# rat.net
KiCad netlist of a schematic drawn in EAGLE
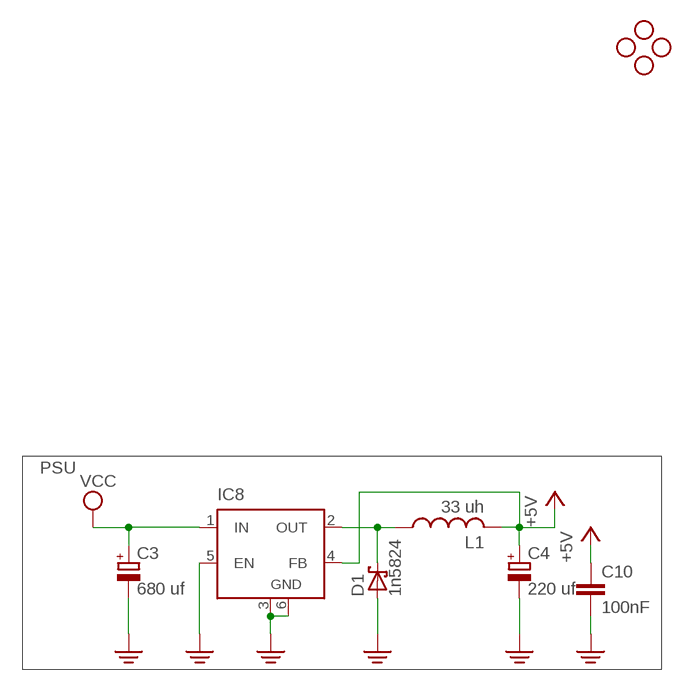
[diagram p0: schematic, sheet 1, part 1 of 2]
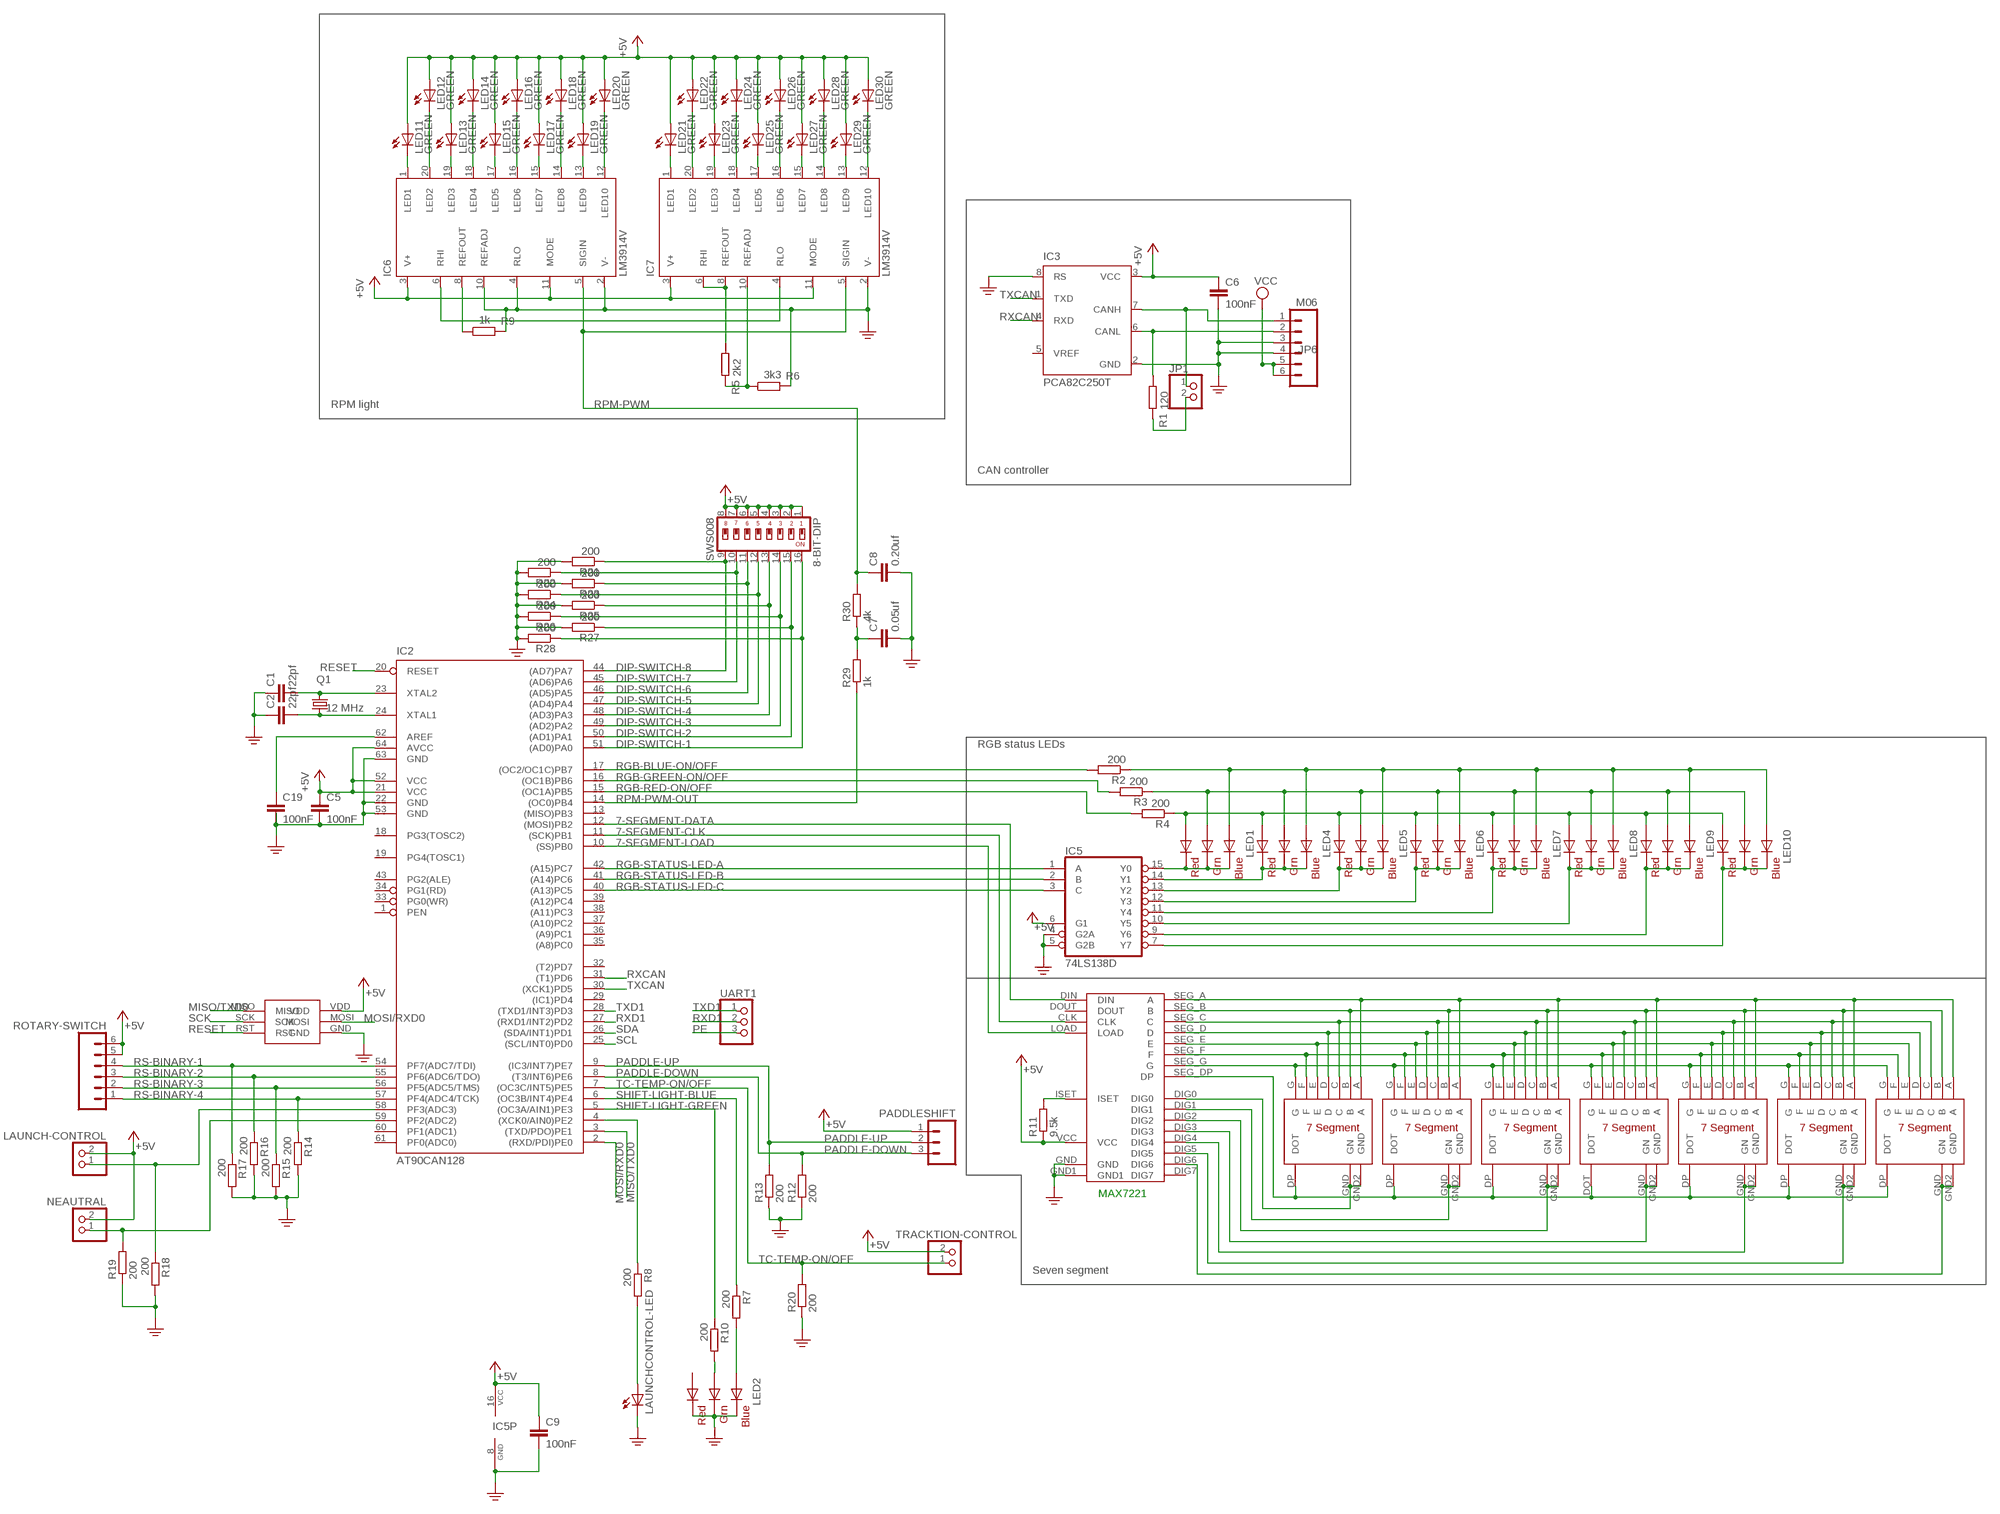
[diagram p1: schematic, sheet 1, part 2 of 2]

(export (version "E")
  (design (tool "Eeschema 10.0.6"))
  (components
    (comp (ref "8-BIT-DIP")
      (value "SWS008")
      (footprint "eagle-import:SMS-008")
      (libsource (lib "eagle-import") (part "SWS008"))
    )
    (comp (ref "C1")
      (value "22pf")
      (footprint "eagle-import:C0603K")
      (libsource (lib "eagle-import") (part "C-EUC0603K"))
    )
    (comp (ref "C2")
      (value "22pf")
      (footprint "eagle-import:C0603K")
      (libsource (lib "eagle-import") (part "C-EUC0603K"))
    )
    (comp (ref "C3")
      (value "680 uf")
      (footprint "eagle-import:E5-10,5")
      (libsource (lib "eagle-import") (part "CPOL-EUE5-10.5"))
    )
    (comp (ref "C4")
      (value "220 uf")
      (footprint "eagle-import:E2,5-7")
      (libsource (lib "eagle-import") (part "CPOL-EUE2.5-7"))
    )
    (comp (ref "C5")
      (value "100nF")
      (footprint "eagle-import:C0603K")
      (libsource (lib "eagle-import") (part "C-EUC0603K"))
    )
    (comp (ref "C6")
      (value "100nF")
      (footprint "eagle-import:C0603K")
      (libsource (lib "eagle-import") (part "C-EUC0603K"))
    )
    (comp (ref "C7")
      (value "0.05uf")
      (footprint "eagle-import:C0603K")
      (libsource (lib "eagle-import") (part "C-EUC0603K"))
    )
    (comp (ref "C8")
      (value "0.20uf")
      (footprint "eagle-import:C0603K")
      (libsource (lib "eagle-import") (part "C-EUC0603K"))
    )
    (comp (ref "C9")
      (value "100nF")
      (footprint "eagle-import:C0603K")
      (libsource (lib "eagle-import") (part "C-EUC0603K"))
    )
    (comp (ref "C10")
      (value "100nF")
      (footprint "eagle-import:C0603K")
      (libsource (lib "eagle-import") (part "C-EUC0603K"))
    )
    (comp (ref "C19")
      (value "100nF")
      (footprint "eagle-import:C0603K")
      (libsource (lib "eagle-import") (part "C-EUC0603K"))
    )
    (comp (ref "D1")
      (value "1n5824")
      (footprint "eagle-import:P6T15")
      (libsource (lib "eagle-import") (part "SCHOTTKY-DIODEP6T15"))
    )
    (comp (ref "IC2")
      (value "AT90CAN128")
      (footprint "eagle-import:TQFP64")
      (fields (field (name "MPN") "ATMEGA128-16AU"))
      (libsource (lib "eagle-import") (part "MEGA128-A"))
    )
    (comp (ref "IC3")
      (value "PCA82C250T")
      (footprint "eagle-import:SO8")
      (libsource (lib "eagle-import") (part "PCA82C250T"))
    )
    (comp (ref "IC5")
      (value "74LS138D")
      (footprint "eagle-import:SO16")
      (libsource (lib "eagle-import") (part "74138DLS"))
    )
    (comp (ref "IC6")
      (value "LM3914V")
      (footprint "eagle-import:PLCC20S")
      (libsource (lib "eagle-import") (part "LM391V4"))
    )
    (comp (ref "IC7")
      (value "LM3914V")
      (footprint "eagle-import:PLCC20S")
      (libsource (lib "eagle-import") (part "LM391V4"))
    )
    (comp (ref "IC8")
      (value "LM2596S")
      (footprint "eagle-import:TO263-5")
      (libsource (lib "eagle-import") (part "LM2596S"))
    )
    (comp (ref "JP1")
      (value "PINHD-1X2")
      (footprint "eagle-import:1X02")
      (libsource (lib "eagle-import") (part "PINHD-1X2"))
    )
    (comp (ref "JP2")
      (value "STAND-OFF")
      (footprint "eagle-import:STAND-OFF")
      (libsource (lib "eagle-import") (part "STAND-OFF"))
    )
    (comp (ref "JP3")
      (value "STAND-OFF")
      (footprint "eagle-import:STAND-OFF")
      (libsource (lib "eagle-import") (part "STAND-OFF"))
    )
    (comp (ref "JP4")
      (value "STAND-OFF")
      (footprint "eagle-import:STAND-OFF")
      (libsource (lib "eagle-import") (part "STAND-OFF"))
    )
    (comp (ref "JP5")
      (value "STAND-OFF")
      (footprint "eagle-import:STAND-OFF")
      (libsource (lib "eagle-import") (part "STAND-OFF"))
    )
    (comp (ref "JP6")
      (value "M06")
      (footprint "eagle-import:S6B_PH")
      (libsource (lib "eagle-import") (part "M06"))
    )
    (comp (ref "L1")
      (value "33 uh")
      (footprint "eagle-import:TFI0410")
      (libsource (lib "eagle-import") (part "L-USTFI0410"))
    )
    (comp (ref "LAUNCH-CONTROL")
      (value "JST_2PIN-SMT-RA")
      (footprint "eagle-import:JST-PH-2-SMT-RA")
      (libsource (lib "eagle-import") (part "JST_2PIN-SMT-RA"))
    )
    (comp (ref "LAUNCHCONTROL-LED")
      (value "LEDSMT1206")
      (footprint "eagle-import:1206")
      (libsource (lib "eagle-import") (part "LEDSMT1206"))
    )
    (comp (ref "LED1")
      (value "RGBLED5050")
      (footprint "eagle-import:RGBLED5050")
      (libsource (lib "eagle-import") (part "RGBLED5050"))
    )
    (comp (ref "LED2")
      (value "RGBLED5050")
      (footprint "eagle-import:RGBLED5050")
      (libsource (lib "eagle-import") (part "RGBLED5050"))
    )
    (comp (ref "LED4")
      (value "RGBLED5050")
      (footprint "eagle-import:RGBLED5050")
      (libsource (lib "eagle-import") (part "RGBLED5050"))
    )
    (comp (ref "LED5")
      (value "RGBLED5050")
      (footprint "eagle-import:RGBLED5050")
      (libsource (lib "eagle-import") (part "RGBLED5050"))
    )
    (comp (ref "LED6")
      (value "RGBLED5050")
      (footprint "eagle-import:RGBLED5050")
      (libsource (lib "eagle-import") (part "RGBLED5050"))
    )
    (comp (ref "LED7")
      (value "RGBLED5050")
      (footprint "eagle-import:RGBLED5050")
      (libsource (lib "eagle-import") (part "RGBLED5050"))
    )
    (comp (ref "LED8")
      (value "RGBLED5050")
      (footprint "eagle-import:RGBLED5050")
      (libsource (lib "eagle-import") (part "RGBLED5050"))
    )
    (comp (ref "LED9")
      (value "RGBLED5050")
      (footprint "eagle-import:RGBLED5050")
      (libsource (lib "eagle-import") (part "RGBLED5050"))
    )
    (comp (ref "LED10")
      (value "RGBLED5050")
      (footprint "eagle-import:RGBLED5050")
      (libsource (lib "eagle-import") (part "RGBLED5050"))
    )
    (comp (ref "LED11")
      (value "GREEN")
      (footprint "eagle-import:1206")
      (libsource (lib "eagle-import") (part "LEDSMT1206"))
    )
    (comp (ref "LED12")
      (value "GREEN")
      (footprint "eagle-import:1206")
      (libsource (lib "eagle-import") (part "LEDSMT1206"))
    )
    (comp (ref "LED13")
      (value "GREEN")
      (footprint "eagle-import:1206")
      (libsource (lib "eagle-import") (part "LEDSMT1206"))
    )
    (comp (ref "LED14")
      (value "GREEN")
      (footprint "eagle-import:1206")
      (libsource (lib "eagle-import") (part "LEDSMT1206"))
    )
    (comp (ref "LED15")
      (value "GREEN")
      (footprint "eagle-import:1206")
      (libsource (lib "eagle-import") (part "LEDSMT1206"))
    )
    (comp (ref "LED16")
      (value "GREEN")
      (footprint "eagle-import:1206")
      (libsource (lib "eagle-import") (part "LEDSMT1206"))
    )
    (comp (ref "LED17")
      (value "GREEN")
      (footprint "eagle-import:1206")
      (libsource (lib "eagle-import") (part "LEDSMT1206"))
    )
    (comp (ref "LED18")
      (value "GREEN")
      (footprint "eagle-import:1206")
      (libsource (lib "eagle-import") (part "LEDSMT1206"))
    )
    (comp (ref "LED19")
      (value "GREEN")
      (footprint "eagle-import:1206")
      (libsource (lib "eagle-import") (part "LEDSMT1206"))
    )
    (comp (ref "LED20")
      (value "GREEN")
      (footprint "eagle-import:1206")
      (libsource (lib "eagle-import") (part "LEDSMT1206"))
    )
    (comp (ref "LED21")
      (value "GREEN")
      (footprint "eagle-import:1206")
      (libsource (lib "eagle-import") (part "LEDSMT1206"))
    )
    (comp (ref "LED22")
      (value "GREEN")
      (footprint "eagle-import:1206")
      (libsource (lib "eagle-import") (part "LEDSMT1206"))
    )
    (comp (ref "LED23")
      (value "GREEN")
      (footprint "eagle-import:1206")
      (libsource (lib "eagle-import") (part "LEDSMT1206"))
    )
    (comp (ref "LED24")
      (value "GREEN")
      (footprint "eagle-import:1206")
      (libsource (lib "eagle-import") (part "LEDSMT1206"))
    )
    (comp (ref "LED25")
      (value "GREEN")
      (footprint "eagle-import:1206")
      (libsource (lib "eagle-import") (part "LEDSMT1206"))
    )
    (comp (ref "LED26")
      (value "GREEN")
      (footprint "eagle-import:1206")
      (libsource (lib "eagle-import") (part "LEDSMT1206"))
    )
    (comp (ref "LED27")
      (value "GREEN")
      (footprint "eagle-import:1206")
      (libsource (lib "eagle-import") (part "LEDSMT1206"))
    )
    (comp (ref "LED28")
      (value "GREEN")
      (footprint "eagle-import:1206")
      (libsource (lib "eagle-import") (part "LEDSMT1206"))
    )
    (comp (ref "LED29")
      (value "GREEN")
      (footprint "eagle-import:1206")
      (libsource (lib "eagle-import") (part "LEDSMT1206"))
    )
    (comp (ref "LED30")
      (value "GREEN")
      (footprint "eagle-import:1206")
      (libsource (lib "eagle-import") (part "LEDSMT1206"))
    )
    (comp (ref "MAX7221")
      (value "MAX7221-SMD")
      (footprint "eagle-import:MAX7221")
      (libsource (lib "eagle-import") (part "MAX7221-SMD"))
    )
    (comp (ref "NEAUTRAL")
      (value "JST_2PIN-SMT-RA")
      (footprint "eagle-import:JST-PH-2-SMT-RA")
      (libsource (lib "eagle-import") (part "JST_2PIN-SMT-RA"))
    )
    (comp (ref "PADDLESHIFT")
      (value "M03")
      (footprint "eagle-import:S3B-PH")
      (libsource (lib "eagle-import") (part "M03"))
    )
    (comp (ref "Q1")
      (value "12 MHz")
      (footprint "eagle-import:HC49U70")
      (libsource (lib "eagle-import") (part "CRYSTALHC49U70"))
    )
    (comp (ref "R1")
      (value "120")
      (footprint "eagle-import:R0603")
      (libsource (lib "eagle-import") (part "resistor_R-EU_R0603"))
    )
    (comp (ref "R2")
      (value "200")
      (footprint "eagle-import:R0603")
      (libsource (lib "eagle-import") (part "R-EU_R0603"))
    )
    (comp (ref "R3")
      (value "200")
      (footprint "eagle-import:R0603")
      (libsource (lib "eagle-import") (part "R-EU_R0603"))
    )
    (comp (ref "R4")
      (value "200")
      (footprint "eagle-import:R0603")
      (libsource (lib "eagle-import") (part "R-EU_R0603"))
    )
    (comp (ref "R5")
      (value "2k2")
      (footprint "eagle-import:R0603")
      (libsource (lib "eagle-import") (part "resistor_R-EU_R0603"))
    )
    (comp (ref "R6")
      (value "3k3")
      (footprint "eagle-import:R0603")
      (libsource (lib "eagle-import") (part "resistor_R-EU_R0603"))
    )
    (comp (ref "R7")
      (value "200")
      (footprint "eagle-import:R0603")
      (libsource (lib "eagle-import") (part "R-EU_R0603"))
    )
    (comp (ref "R8")
      (value "200")
      (footprint "eagle-import:R0603")
      (libsource (lib "eagle-import") (part "R-EU_R0603"))
    )
    (comp (ref "R9")
      (value "1k")
      (footprint "eagle-import:R0603")
      (libsource (lib "eagle-import") (part "resistor_R-EU_R0603"))
    )
    (comp (ref "R10")
      (value "200")
      (footprint "eagle-import:R0603")
      (libsource (lib "eagle-import") (part "R-EU_R0603"))
    )
    (comp (ref "R11")
      (value "9.5k")
      (footprint "eagle-import:R0603")
      (libsource (lib "eagle-import") (part "R-EU_R0603"))
    )
    (comp (ref "R12")
      (value "200")
      (footprint "eagle-import:R0603")
      (libsource (lib "eagle-import") (part "R-EU_R0603"))
    )
    (comp (ref "R13")
      (value "200")
      (footprint "eagle-import:R0603")
      (libsource (lib "eagle-import") (part "R-EU_R0603"))
    )
    (comp (ref "R14")
      (value "200")
      (footprint "eagle-import:R0603")
      (libsource (lib "eagle-import") (part "R-EU_R0603"))
    )
    (comp (ref "R15")
      (value "200")
      (footprint "eagle-import:R0603")
      (libsource (lib "eagle-import") (part "R-EU_R0603"))
    )
    (comp (ref "R16")
      (value "200")
      (footprint "eagle-import:R0603")
      (libsource (lib "eagle-import") (part "R-EU_R0603"))
    )
    (comp (ref "R17")
      (value "200")
      (footprint "eagle-import:R0603")
      (libsource (lib "eagle-import") (part "R-EU_R0603"))
    )
    (comp (ref "R18")
      (value "200")
      (footprint "eagle-import:R0603")
      (libsource (lib "eagle-import") (part "R-EU_R0603"))
    )
    (comp (ref "R19")
      (value "200")
      (footprint "eagle-import:R0603")
      (libsource (lib "eagle-import") (part "R-EU_R0603"))
    )
    (comp (ref "R20")
      (value "200")
      (footprint "eagle-import:R0603")
      (libsource (lib "eagle-import") (part "R-EU_R0603"))
    )
    (comp (ref "R21")
      (value "200")
      (footprint "eagle-import:R0603")
      (libsource (lib "eagle-import") (part "R-EU_R0603"))
    )
    (comp (ref "R22")
      (value "200")
      (footprint "eagle-import:R0603")
      (libsource (lib "eagle-import") (part "R-EU_R0603"))
    )
    (comp (ref "R23")
      (value "200")
      (footprint "eagle-import:R0603")
      (libsource (lib "eagle-import") (part "R-EU_R0603"))
    )
    (comp (ref "R24")
      (value "200")
      (footprint "eagle-import:R0603")
      (libsource (lib "eagle-import") (part "R-EU_R0603"))
    )
    (comp (ref "R25")
      (value "200")
      (footprint "eagle-import:R0603")
      (libsource (lib "eagle-import") (part "R-EU_R0603"))
    )
    (comp (ref "R26")
      (value "200")
      (footprint "eagle-import:R0603")
      (libsource (lib "eagle-import") (part "R-EU_R0603"))
    )
    (comp (ref "R27")
      (value "200")
      (footprint "eagle-import:R0603")
      (libsource (lib "eagle-import") (part "R-EU_R0603"))
    )
    (comp (ref "R28")
      (value "200")
      (footprint "eagle-import:R0603")
      (libsource (lib "eagle-import") (part "R-EU_R0603"))
    )
    (comp (ref "R29")
      (value "1k")
      (footprint "eagle-import:R0603")
      (libsource (lib "eagle-import") (part "R-EU_R0603"))
    )
    (comp (ref "R30")
      (value "4k")
      (footprint "eagle-import:R0603")
      (libsource (lib "eagle-import") (part "R-EU_R0603"))
    )
    (comp (ref "ROTARY-SWITCH")
      (value "M06")
      (footprint "eagle-import:S6B_PH")
      (libsource (lib "eagle-import") (part "M06"))
    )
    (comp (ref "TRACKTION-CONTROL")
      (value "JST_2PIN-SMT-RA")
      (footprint "eagle-import:JST-PH-2-SMT-RA")
      (libsource (lib "eagle-import") (part "JST_2PIN-SMT-RA"))
    )
    (comp (ref "U$2")
      (value "REDSEVENSEGMENT")
      (footprint "eagle-import:REDSEGMENT")
      (libsource (lib "eagle-import") (part "REDSEVENSEGMENT"))
    )
    (comp (ref "U$3")
      (value "REDSEVENSEGMENT")
      (footprint "eagle-import:REDSEGMENT")
      (libsource (lib "eagle-import") (part "REDSEVENSEGMENT"))
    )
    (comp (ref "U$4")
      (value "REDSEVENSEGMENT")
      (footprint "eagle-import:REDSEGMENT")
      (libsource (lib "eagle-import") (part "REDSEVENSEGMENT"))
    )
    (comp (ref "U$5")
      (value "BIGSEVENSEGMENT")
      (footprint "eagle-import:BIGSEVENSEGMENT")
      (libsource (lib "eagle-import") (part "BIGSEVENSEGMENT"))
    )
    (comp (ref "U$6")
      (value "REDSEVENSEGMENT")
      (footprint "eagle-import:REDSEGMENT")
      (libsource (lib "eagle-import") (part "REDSEVENSEGMENT"))
    )
    (comp (ref "U$7")
      (value "REDSEVENSEGMENT")
      (footprint "eagle-import:REDSEGMENT")
      (libsource (lib "eagle-import") (part "REDSEVENSEGMENT"))
    )
    (comp (ref "U$8")
      (value "REDSEVENSEGMENT")
      (footprint "eagle-import:REDSEGMENT")
      (libsource (lib "eagle-import") (part "REDSEVENSEGMENT"))
    )
    (comp (ref "U$9")
      (value "ISP-HEADER")
      (footprint "eagle-import:ISP-HEADER")
      (libsource (lib "eagle-import") (part "ISP-HEADER"))
    )
    (comp (ref "UART1")
      (value "PINHD-1X3")
      (footprint "eagle-import:1X03")
      (libsource (lib "eagle-import") (part "PINHD-1X3"))
    )
  )
  (nets
    (net (code "1") (name "+5V") (class "Default")
      (node (ref "8-BIT-DIP") (pin "1") (pinfunction "1_1") (pintype "passive"))
      (node (ref "8-BIT-DIP") (pin "2") (pinfunction "2_2") (pintype "passive"))
      (node (ref "8-BIT-DIP") (pin "3") (pinfunction "3_3") (pintype "passive"))
      (node (ref "8-BIT-DIP") (pin "4") (pinfunction "4_4") (pintype "passive"))
      (node (ref "8-BIT-DIP") (pin "5") (pinfunction "5_5") (pintype "passive"))
      (node (ref "8-BIT-DIP") (pin "6") (pinfunction "6_6") (pintype "passive"))
      (node (ref "8-BIT-DIP") (pin "7") (pinfunction "7_7") (pintype "passive"))
      (node (ref "8-BIT-DIP") (pin "8") (pinfunction "8_8") (pintype "passive"))
      (node (ref "C10") (pin "1") (pinfunction "1_1") (pintype "passive"))
      (node (ref "C4") (pin "+") (pinfunction "+_+") (pintype "passive"))
      (node (ref "C5") (pin "1") (pinfunction "1_1") (pintype "passive"))
      (node (ref "C6") (pin "1") (pinfunction "1_1") (pintype "passive"))
      (node (ref "C9") (pin "1") (pinfunction "1_1") (pintype "passive"))
      (node (ref "IC2") (pin "21") (pinfunction "VCC_21") (pintype "power_in"))
      (node (ref "IC2") (pin "52") (pinfunction "VCC_52") (pintype "power_in"))
      (node (ref "IC2") (pin "64") (pinfunction "AVCC_64") (pintype "power_in"))
      (node (ref "IC3") (pin "3") (pinfunction "VCC_3") (pintype "power_in"))
      (node (ref "IC5") (pin "16") (pinfunction "VCC_16") (pintype "power_in"))
      (node (ref "IC5") (pin "6") (pinfunction "G1_6") (pintype "input"))
      (node (ref "IC6") (pin "11") (pinfunction "MODE_11") (pintype "input"))
      (node (ref "IC6") (pin "3") (pinfunction "V+_3") (pintype "power_in"))
      (node (ref "IC7") (pin "11") (pinfunction "MODE_11") (pintype "input"))
      (node (ref "IC7") (pin "3") (pinfunction "V+_3") (pintype "power_in"))
      (node (ref "IC8") (pin "4") (pinfunction "FB_4") (pintype "input"))
      (node (ref "L1") (pin "2") (pinfunction "2_2") (pintype "passive"))
      (node (ref "LAUNCH-CONTROL") (pin "2") (pinfunction "1_2") (pintype "passive"))
      (node (ref "LED11") (pin "A") (pinfunction "A_A") (pintype "passive"))
      (node (ref "LED12") (pin "A") (pinfunction "A_A") (pintype "passive"))
      (node (ref "LED13") (pin "A") (pinfunction "A_A") (pintype "passive"))
      (node (ref "LED14") (pin "A") (pinfunction "A_A") (pintype "passive"))
      (node (ref "LED15") (pin "A") (pinfunction "A_A") (pintype "passive"))
      (node (ref "LED16") (pin "A") (pinfunction "A_A") (pintype "passive"))
      (node (ref "LED17") (pin "A") (pinfunction "A_A") (pintype "passive"))
      (node (ref "LED18") (pin "A") (pinfunction "A_A") (pintype "passive"))
      (node (ref "LED19") (pin "A") (pinfunction "A_A") (pintype "passive"))
      (node (ref "LED20") (pin "A") (pinfunction "A_A") (pintype "passive"))
      (node (ref "LED21") (pin "A") (pinfunction "A_A") (pintype "passive"))
      (node (ref "LED22") (pin "A") (pinfunction "A_A") (pintype "passive"))
      (node (ref "LED23") (pin "A") (pinfunction "A_A") (pintype "passive"))
      (node (ref "LED24") (pin "A") (pinfunction "A_A") (pintype "passive"))
      (node (ref "LED25") (pin "A") (pinfunction "A_A") (pintype "passive"))
      (node (ref "LED26") (pin "A") (pinfunction "A_A") (pintype "passive"))
      (node (ref "LED27") (pin "A") (pinfunction "A_A") (pintype "passive"))
      (node (ref "LED28") (pin "A") (pinfunction "A_A") (pintype "passive"))
      (node (ref "LED29") (pin "A") (pinfunction "A_A") (pintype "passive"))
      (node (ref "LED30") (pin "A") (pinfunction "A_A") (pintype "passive"))
      (node (ref "MAX7221") (pin "VCC") (pinfunction "VCC_VCC") (pintype "bidirectional"))
      (node (ref "NEAUTRAL") (pin "2") (pinfunction "1_2") (pintype "passive"))
      (node (ref "PADDLESHIFT") (pin "1") (pinfunction "1_1") (pintype "passive"))
      (node (ref "R11") (pin "1") (pinfunction "1_1") (pintype "passive"))
      (node (ref "ROTARY-SWITCH") (pin "5") (pinfunction "5_5") (pintype "passive"))
      (node (ref "ROTARY-SWITCH") (pin "6") (pinfunction "6_6") (pintype "passive"))
      (node (ref "TRACKTION-CONTROL") (pin "2") (pinfunction "1_2") (pintype "passive"))
      (node (ref "U$9") (pin "VDD") (pinfunction "VDD_VDD") (pintype "bidirectional"))
    )
    (net (code "2") (name "/7-SEGMENT-CLK") (class "Default")
      (node (ref "IC2") (pin "11") (pinfunction "(SCK)PB1_11") (pintype "bidirectional"))
      (node (ref "MAX7221") (pin "CLK") (pinfunction "CLK_CLK") (pintype "bidirectional"))
    )
    (net (code "3") (name "/7-SEGMENT-DATA") (class "Default")
      (node (ref "IC2") (pin "12") (pinfunction "(MOSI)PB2_12") (pintype "bidirectional"))
      (node (ref "MAX7221") (pin "DIN") (pinfunction "DIN_DIN") (pintype "bidirectional"))
    )
    (net (code "4") (name "/7-SEGMENT-LOAD") (class "Default")
      (node (ref "IC2") (pin "10") (pinfunction "(SS)PB0_10") (pintype "bidirectional"))
      (node (ref "MAX7221") (pin "LOAD") (pinfunction "LOAD_LOAD") (pintype "bidirectional"))
    )
    (net (code "5") (name "/DIP-SWITCH-1") (class "Default")
      (node (ref "8-BIT-DIP") (pin "16") (pinfunction "16_16") (pintype "passive"))
      (node (ref "IC2") (pin "51") (pinfunction "(AD0)PA0_51") (pintype "bidirectional"))
      (node (ref "R28") (pin "1") (pinfunction "1_1") (pintype "passive"))
    )
    (net (code "6") (name "/DIP-SWITCH-2") (class "Default")
      (node (ref "8-BIT-DIP") (pin "15") (pinfunction "15_15") (pintype "passive"))
      (node (ref "IC2") (pin "50") (pinfunction "(AD1)PA1_50") (pintype "bidirectional"))
      (node (ref "R27") (pin "1") (pinfunction "1_1") (pintype "passive"))
    )
    (net (code "7") (name "/DIP-SWITCH-3") (class "Default")
      (node (ref "8-BIT-DIP") (pin "14") (pinfunction "14_14") (pintype "passive"))
      (node (ref "IC2") (pin "49") (pinfunction "(AD2)PA2_49") (pintype "bidirectional"))
      (node (ref "R26") (pin "1") (pinfunction "1_1") (pintype "passive"))
    )
    (net (code "8") (name "/DIP-SWITCH-4") (class "Default")
      (node (ref "8-BIT-DIP") (pin "13") (pinfunction "13_13") (pintype "passive"))
      (node (ref "IC2") (pin "48") (pinfunction "(AD3)PA3_48") (pintype "bidirectional"))
      (node (ref "R25") (pin "1") (pinfunction "1_1") (pintype "passive"))
    )
    (net (code "9") (name "/DIP-SWITCH-5") (class "Default")
      (node (ref "8-BIT-DIP") (pin "12") (pinfunction "12_12") (pintype "passive"))
      (node (ref "IC2") (pin "47") (pinfunction "(AD4)PA4_47") (pintype "bidirectional"))
      (node (ref "R24") (pin "1") (pinfunction "1_1") (pintype "passive"))
    )
    (net (code "10") (name "/DIP-SWITCH-6") (class "Default")
      (node (ref "8-BIT-DIP") (pin "11") (pinfunction "11_11") (pintype "passive"))
      (node (ref "IC2") (pin "46") (pinfunction "(AD5)PA5_46") (pintype "bidirectional"))
      (node (ref "R23") (pin "1") (pinfunction "1_1") (pintype "passive"))
    )
    (net (code "11") (name "/DIP-SWITCH-7") (class "Default")
      (node (ref "8-BIT-DIP") (pin "10") (pinfunction "10_10") (pintype "passive"))
      (node (ref "IC2") (pin "45") (pinfunction "(AD6)PA6_45") (pintype "bidirectional"))
      (node (ref "R22") (pin "1") (pinfunction "1_1") (pintype "passive"))
    )
    (net (code "12") (name "/DIP-SWITCH-8") (class "Default")
      (node (ref "8-BIT-DIP") (pin "9") (pinfunction "9_9") (pintype "passive"))
      (node (ref "IC2") (pin "44") (pinfunction "(AD7)PA7_44") (pintype "bidirectional"))
      (node (ref "R21") (pin "1") (pinfunction "1_1") (pintype "passive"))
    )
    (net (code "13") (name "/MISO{slash}TXD0") (class "Default")
      (node (ref "IC2") (pin "3") (pinfunction "(TXD/PDO)PE1_3") (pintype "bidirectional"))
      (node (ref "U$9") (pin "MISO") (pinfunction "MISO_MISO") (pintype "bidirectional"))
    )
    (net (code "14") (name "/MOSI{slash}RXD0") (class "Default")
      (node (ref "IC2") (pin "2") (pinfunction "(RXD/PDI)PE0_2") (pintype "bidirectional"))
      (node (ref "U$9") (pin "MOSI") (pinfunction "MOSI_MOSI") (pintype "bidirectional"))
    )
    (net (code "15") (name "/PADDLE-DOWN") (class "Default")
      (node (ref "IC2") (pin "8") (pinfunction "(T3/INT6)PE6_8") (pintype "bidirectional"))
      (node (ref "PADDLESHIFT") (pin "3") (pinfunction "3_3") (pintype "passive"))
      (node (ref "R12") (pin "2") (pinfunction "2_2") (pintype "passive"))
    )
    (net (code "16") (name "/PADDLE-UP") (class "Default")
      (node (ref "IC2") (pin "9") (pinfunction "(IC3/INT7)PE7_9") (pintype "bidirectional"))
      (node (ref "PADDLESHIFT") (pin "2") (pinfunction "2_2") (pintype "passive"))
      (node (ref "R13") (pin "2") (pinfunction "2_2") (pintype "passive"))
    )
    (net (code "17") (name "/RESET") (class "Default")
      (node (ref "IC2") (pin "20") (pinfunction "RESET_20") (pintype "input"))
      (node (ref "U$9") (pin "RST") (pinfunction "RST_RST") (pintype "bidirectional"))
    )
    (net (code "18") (name "/RGB-BLUE-ON{slash}OFF") (class "Default")
      (node (ref "IC2") (pin "17") (pinfunction "(OC2/OC1C)PB7_17") (pintype "bidirectional"))
      (node (ref "R2") (pin "2") (pinfunction "2_2") (pintype "passive"))
    )
    (net (code "19") (name "/RGB-GREEN-ON{slash}OFF") (class "Default")
      (node (ref "IC2") (pin "16") (pinfunction "(OC1B)PB6_16") (pintype "bidirectional"))
      (node (ref "R3") (pin "2") (pinfunction "2_2") (pintype "passive"))
    )
    (net (code "20") (name "/RGB-RED-ON{slash}OFF") (class "Default")
      (node (ref "IC2") (pin "15") (pinfunction "(OC1A)PB5_15") (pintype "bidirectional"))
      (node (ref "R4") (pin "2") (pinfunction "2_2") (pintype "passive"))
    )
    (net (code "21") (name "/RGB-STATUS-LED-A") (class "Default")
      (node (ref "IC2") (pin "42") (pinfunction "(A15)PC7_42") (pintype "output"))
      (node (ref "IC5") (pin "1") (pinfunction "A_1") (pintype "input"))
    )
    (net (code "22") (name "/RGB-STATUS-LED-B") (class "Default")
      (node (ref "IC2") (pin "41") (pinfunction "(A14)PC6_41") (pintype "output"))
      (node (ref "IC5") (pin "2") (pinfunction "B_2") (pintype "input"))
    )
    (net (code "23") (name "/RGB-STATUS-LED-C") (class "Default")
      (node (ref "IC2") (pin "40") (pinfunction "(A13)PC5_40") (pintype "output"))
      (node (ref "IC5") (pin "3") (pinfunction "C_3") (pintype "input"))
    )
    (net (code "24") (name "/RPM-PWM") (class "Default")
      (node (ref "C8") (pin "1") (pinfunction "1_1") (pintype "passive"))
      (node (ref "IC6") (pin "5") (pinfunction "SIGIN_5") (pintype "input"))
      (node (ref "IC7") (pin "5") (pinfunction "SIGIN_5") (pintype "input"))
      (node (ref "R30") (pin "2") (pinfunction "2_2") (pintype "passive"))
    )
    (net (code "25") (name "/RPM-PWM-OUT") (class "Default")
      (node (ref "IC2") (pin "14") (pinfunction "(OC0)PB4_14") (pintype "bidirectional"))
      (node (ref "R29") (pin "1") (pinfunction "1_1") (pintype "passive"))
    )
    (net (code "26") (name "/RS-BINARY-1") (class "Default")
      (node (ref "IC2") (pin "54") (pinfunction "PF7(ADC7/TDI)_54") (pintype "input"))
      (node (ref "R17") (pin "1") (pinfunction "1_1") (pintype "passive"))
      (node (ref "ROTARY-SWITCH") (pin "4") (pinfunction "4_4") (pintype "passive"))
    )
    (net (code "27") (name "/RS-BINARY-2") (class "Default")
      (node (ref "IC2") (pin "55") (pinfunction "PF6(ADC6/TDO)_55") (pintype "input"))
      (node (ref "R16") (pin "1") (pinfunction "1_1") (pintype "passive"))
      (node (ref "ROTARY-SWITCH") (pin "3") (pinfunction "3_3") (pintype "passive"))
    )
    (net (code "28") (name "/RS-BINARY-3") (class "Default")
      (node (ref "IC2") (pin "56") (pinfunction "PF5(ADC5/TMS)_56") (pintype "input"))
      (node (ref "R15") (pin "1") (pinfunction "1_1") (pintype "passive"))
      (node (ref "ROTARY-SWITCH") (pin "2") (pinfunction "2_2") (pintype "passive"))
    )
    (net (code "29") (name "/RS-BINARY-4") (class "Default")
      (node (ref "IC2") (pin "57") (pinfunction "PF4(ADC4/TCK)_57") (pintype "input"))
      (node (ref "R14") (pin "1") (pinfunction "1_1") (pintype "passive"))
      (node (ref "ROTARY-SWITCH") (pin "1") (pinfunction "1_1") (pintype "passive"))
    )
    (net (code "30") (name "/RXCAN") (class "Default")
      (node (ref "IC2") (pin "31") (pinfunction "(T1)PD6_31") (pintype "bidirectional"))
      (node (ref "IC3") (pin "4") (pinfunction "RXD_4") (pintype "output"))
    )
    (net (code "31") (name "/RXD1") (class "Default")
      (node (ref "IC2") (pin "27") (pinfunction "(RXD1/INT2)PD2_27") (pintype "bidirectional"))
      (node (ref "UART1") (pin "2") (pinfunction "2_2") (pintype "passive"))
    )
    (net (code "32") (name "/SCK") (class "Default")
      (node (ref "U$9") (pin "SCK") (pinfunction "SCK_SCK") (pintype "bidirectional"))
    )
    (net (code "33") (name "/SCL") (class "Default")
      (node (ref "IC2") (pin "25") (pinfunction "(SCL/INT0)PD0_25") (pintype "bidirectional"))
    )
    (net (code "34") (name "/SDA") (class "Default")
      (node (ref "IC2") (pin "26") (pinfunction "(SDA/INT1)PD1_26") (pintype "bidirectional"))
    )
    (net (code "35") (name "/SHIFT-LIGHT-BLUE") (class "Default")
      (node (ref "IC2") (pin "6") (pinfunction "(OC3B/INT4)PE4_6") (pintype "bidirectional"))
      (node (ref "R7") (pin "1") (pinfunction "1_1") (pintype "passive"))
    )
    (net (code "36") (name "/SHIFT-LIGHT-GREEN") (class "Default")
      (node (ref "IC2") (pin "5") (pinfunction "(OC3A/AIN1)PE3_5") (pintype "bidirectional"))
      (node (ref "R10") (pin "1") (pinfunction "1_1") (pintype "passive"))
    )
    (net (code "37") (name "/TC-TEMP-ON{slash}OFF") (class "Default")
      (node (ref "IC2") (pin "7") (pinfunction "(OC3C/INT5)PE5_7") (pintype "bidirectional"))
      (node (ref "R20") (pin "2") (pinfunction "2_2") (pintype "passive"))
      (node (ref "TRACKTION-CONTROL") (pin "1") (pinfunction "2_1") (pintype "passive"))
    )
    (net (code "38") (name "/TXCAN") (class "Default")
      (node (ref "IC2") (pin "30") (pinfunction "(XCK1)PD5_30") (pintype "bidirectional"))
      (node (ref "IC3") (pin "1") (pinfunction "TXD_1") (pintype "input"))
    )
    (net (code "39") (name "/TXD1") (class "Default")
      (node (ref "IC2") (pin "28") (pinfunction "(TXD1/INT3)PD3_28") (pintype "bidirectional"))
      (node (ref "UART1") (pin "1") (pinfunction "1_1") (pintype "passive"))
    )
    (net (code "40") (name "Net-(C7-Pad1)") (class "Default")
      (node (ref "C7") (pin "1") (pinfunction "1_1") (pintype "passive"))
      (node (ref "R29") (pin "2") (pinfunction "2_2") (pintype "passive"))
      (node (ref "R30") (pin "1") (pinfunction "1_1") (pintype "passive"))
    )
    (net (code "41") (name "Net-(IC2-(XCK0{slash}AIN0)PE2)") (class "Default")
      (node (ref "IC2") (pin "4") (pinfunction "(XCK0/AIN0)PE2_4") (pintype "bidirectional"))
      (node (ref "R8") (pin "1") (pinfunction "1_1") (pintype "passive"))
    )
    (net (code "42") (name "Net-(IC2-AREF)") (class "Default")
      (node (ref "C19") (pin "1") (pinfunction "1_1") (pintype "passive"))
      (node (ref "IC2") (pin "62") (pinfunction "AREF_62") (pintype "passive"))
    )
    (net (code "43") (name "Net-(IC2-PF2(ADC2))") (class "Default")
      (node (ref "IC2") (pin "59") (pinfunction "PF2(ADC2)_59") (pintype "input"))
      (node (ref "NEAUTRAL") (pin "1") (pinfunction "2_1") (pintype "passive"))
      (node (ref "R19") (pin "2") (pinfunction "2_2") (pintype "passive"))
    )
    (net (code "44") (name "Net-(IC2-PF3(ADC3))") (class "Default")
      (node (ref "IC2") (pin "58") (pinfunction "PF3(ADC3)_58") (pintype "input"))
      (node (ref "LAUNCH-CONTROL") (pin "1") (pinfunction "2_1") (pintype "passive"))
      (node (ref "R18") (pin "1") (pinfunction "1_1") (pintype "passive"))
    )
    (net (code "45") (name "Net-(IC2-XTAL1)") (class "Default")
      (node (ref "C2") (pin "2") (pinfunction "2_2") (pintype "passive"))
      (node (ref "IC2") (pin "24") (pinfunction "XTAL1_24") (pintype "bidirectional"))
      (node (ref "Q1") (pin "1") (pinfunction "1_1") (pintype "passive"))
    )
    (net (code "46") (name "Net-(IC2-XTAL2)") (class "Default")
      (node (ref "C1") (pin "2") (pinfunction "2_2") (pintype "passive"))
      (node (ref "IC2") (pin "23") (pinfunction "XTAL2_23") (pintype "bidirectional"))
      (node (ref "Q1") (pin "2") (pinfunction "2_2") (pintype "passive"))
    )
    (net (code "47") (name "Net-(IC3-CANH)") (class "Default")
      (node (ref "IC3") (pin "7") (pinfunction "CANH_7") (pintype "bidirectional"))
      (node (ref "JP1") (pin "1") (pinfunction "1_1") (pintype "passive"))
      (node (ref "JP6") (pin "1") (pinfunction "1_1") (pintype "passive"))
    )
    (net (code "48") (name "Net-(IC3-CANL)") (class "Default")
      (node (ref "IC3") (pin "6") (pinfunction "CANL_6") (pintype "bidirectional"))
      (node (ref "JP6") (pin "2") (pinfunction "2_2") (pintype "passive"))
      (node (ref "R1") (pin "1") (pinfunction "1_1") (pintype "passive"))
    )
    (net (code "49") (name "Net-(IC5A-Y0)") (class "Default")
      (node (ref "IC5") (pin "15") (pinfunction "Y0_15") (pintype "output"))
      (node (ref "LED1") (pin "4") (pinfunction "BLUE_C_4") (pintype "bidirectional"))
      (node (ref "LED1") (pin "5") (pinfunction "RED_C_5") (pintype "bidirectional"))
      (node (ref "LED1") (pin "6") (pinfunction "GREEN_C_6") (pintype "bidirectional"))
    )
    (net (code "50") (name "Net-(IC5A-Y1)") (class "Default")
      (node (ref "IC5") (pin "14") (pinfunction "Y1_14") (pintype "output"))
      (node (ref "LED4") (pin "4") (pinfunction "BLUE_C_4") (pintype "bidirectional"))
      (node (ref "LED4") (pin "5") (pinfunction "RED_C_5") (pintype "bidirectional"))
      (node (ref "LED4") (pin "6") (pinfunction "GREEN_C_6") (pintype "bidirectional"))
    )
    (net (code "51") (name "Net-(IC5A-Y2)") (class "Default")
      (node (ref "IC5") (pin "13") (pinfunction "Y2_13") (pintype "output"))
      (node (ref "LED5") (pin "4") (pinfunction "BLUE_C_4") (pintype "bidirectional"))
      (node (ref "LED5") (pin "5") (pinfunction "RED_C_5") (pintype "bidirectional"))
      (node (ref "LED5") (pin "6") (pinfunction "GREEN_C_6") (pintype "bidirectional"))
    )
    (net (code "52") (name "Net-(IC5A-Y3)") (class "Default")
      (node (ref "IC5") (pin "12") (pinfunction "Y3_12") (pintype "output"))
      (node (ref "LED6") (pin "4") (pinfunction "BLUE_C_4") (pintype "bidirectional"))
      (node (ref "LED6") (pin "5") (pinfunction "RED_C_5") (pintype "bidirectional"))
      (node (ref "LED6") (pin "6") (pinfunction "GREEN_C_6") (pintype "bidirectional"))
    )
    (net (code "53") (name "Net-(IC5A-Y4)") (class "Default")
      (node (ref "IC5") (pin "11") (pinfunction "Y4_11") (pintype "output"))
      (node (ref "LED7") (pin "4") (pinfunction "BLUE_C_4") (pintype "bidirectional"))
      (node (ref "LED7") (pin "5") (pinfunction "RED_C_5") (pintype "bidirectional"))
      (node (ref "LED7") (pin "6") (pinfunction "GREEN_C_6") (pintype "bidirectional"))
    )
    (net (code "54") (name "Net-(IC5A-Y5)") (class "Default")
      (node (ref "IC5") (pin "10") (pinfunction "Y5_10") (pintype "output"))
      (node (ref "LED8") (pin "4") (pinfunction "BLUE_C_4") (pintype "bidirectional"))
      (node (ref "LED8") (pin "5") (pinfunction "RED_C_5") (pintype "bidirectional"))
      (node (ref "LED8") (pin "6") (pinfunction "GREEN_C_6") (pintype "bidirectional"))
    )
    (net (code "55") (name "Net-(IC5A-Y6)") (class "Default")
      (node (ref "IC5") (pin "9") (pinfunction "Y6_9") (pintype "output"))
      (node (ref "LED9") (pin "4") (pinfunction "BLUE_C_4") (pintype "bidirectional"))
      (node (ref "LED9") (pin "5") (pinfunction "RED_C_5") (pintype "bidirectional"))
      (node (ref "LED9") (pin "6") (pinfunction "GREEN_C_6") (pintype "bidirectional"))
    )
    (net (code "56") (name "Net-(IC5A-Y7)") (class "Default")
      (node (ref "IC5") (pin "7") (pinfunction "Y7_7") (pintype "output"))
      (node (ref "LED10") (pin "4") (pinfunction "BLUE_C_4") (pintype "bidirectional"))
      (node (ref "LED10") (pin "5") (pinfunction "RED_C_5") (pintype "bidirectional"))
      (node (ref "LED10") (pin "6") (pinfunction "GREEN_C_6") (pintype "bidirectional"))
    )
    (net (code "57") (name "Net-(IC6-LED1)") (class "Default")
      (node (ref "IC6") (pin "1") (pinfunction "LED1_1") (pintype "output"))
      (node (ref "LED11") (pin "C") (pinfunction "C_C") (pintype "passive"))
    )
    (net (code "58") (name "Net-(IC6-LED2)") (class "Default")
      (node (ref "IC6") (pin "20") (pinfunction "LED2_20") (pintype "output"))
      (node (ref "LED12") (pin "C") (pinfunction "C_C") (pintype "passive"))
    )
    (net (code "59") (name "Net-(IC6-LED3)") (class "Default")
      (node (ref "IC6") (pin "19") (pinfunction "LED3_19") (pintype "output"))
      (node (ref "LED13") (pin "C") (pinfunction "C_C") (pintype "passive"))
    )
    (net (code "60") (name "Net-(IC6-LED4)") (class "Default")
      (node (ref "IC6") (pin "18") (pinfunction "LED4_18") (pintype "output"))
      (node (ref "LED14") (pin "C") (pinfunction "C_C") (pintype "passive"))
    )
    (net (code "61") (name "Net-(IC6-LED5)") (class "Default")
      (node (ref "IC6") (pin "17") (pinfunction "LED5_17") (pintype "output"))
      (node (ref "LED15") (pin "C") (pinfunction "C_C") (pintype "passive"))
    )
    (net (code "62") (name "Net-(IC6-LED6)") (class "Default")
      (node (ref "IC6") (pin "16") (pinfunction "LED6_16") (pintype "output"))
      (node (ref "LED16") (pin "C") (pinfunction "C_C") (pintype "passive"))
    )
    (net (code "63") (name "Net-(IC6-LED7)") (class "Default")
      (node (ref "IC6") (pin "15") (pinfunction "LED7_15") (pintype "output"))
      (node (ref "LED17") (pin "C") (pinfunction "C_C") (pintype "passive"))
    )
    (net (code "64") (name "Net-(IC6-LED8)") (class "Default")
      (node (ref "IC6") (pin "14") (pinfunction "LED8_14") (pintype "output"))
      (node (ref "LED18") (pin "C") (pinfunction "C_C") (pintype "passive"))
    )
    (net (code "65") (name "Net-(IC6-LED9)") (class "Default")
      (node (ref "IC6") (pin "13") (pinfunction "LED9_13") (pintype "output"))
      (node (ref "LED19") (pin "C") (pinfunction "C_C") (pintype "passive"))
    )
    (net (code "66") (name "Net-(IC6-LED10)") (class "Default")
      (node (ref "IC6") (pin "12") (pinfunction "LED10_12") (pintype "output"))
      (node (ref "LED20") (pin "C") (pinfunction "C_C") (pintype "passive"))
    )
    (net (code "67") (name "Net-(IC6-REFOUT)") (class "Default")
      (node (ref "IC6") (pin "8") (pinfunction "REFOUT_8") (pintype "output"))
      (node (ref "R9") (pin "1") (pinfunction "1_1") (pintype "passive"))
    )
    (net (code "68") (name "Net-(IC6-RHI)") (class "Default")
      (node (ref "IC6") (pin "6") (pinfunction "RHI_6") (pintype "input"))
      (node (ref "IC7") (pin "4") (pinfunction "RLO_4") (pintype "input"))
    )
    (net (code "69") (name "Net-(IC7-LED1)") (class "Default")
      (node (ref "IC7") (pin "1") (pinfunction "LED1_1") (pintype "output"))
      (node (ref "LED21") (pin "C") (pinfunction "C_C") (pintype "passive"))
    )
    (net (code "70") (name "Net-(IC7-LED2)") (class "Default")
      (node (ref "IC7") (pin "20") (pinfunction "LED2_20") (pintype "output"))
      (node (ref "LED22") (pin "C") (pinfunction "C_C") (pintype "passive"))
    )
    (net (code "71") (name "Net-(IC7-LED3)") (class "Default")
      (node (ref "IC7") (pin "19") (pinfunction "LED3_19") (pintype "output"))
      (node (ref "LED23") (pin "C") (pinfunction "C_C") (pintype "passive"))
    )
    (net (code "72") (name "Net-(IC7-LED4)") (class "Default")
      (node (ref "IC7") (pin "18") (pinfunction "LED4_18") (pintype "output"))
      (node (ref "LED24") (pin "C") (pinfunction "C_C") (pintype "passive"))
    )
    (net (code "73") (name "Net-(IC7-LED5)") (class "Default")
      (node (ref "IC7") (pin "17") (pinfunction "LED5_17") (pintype "output"))
      (node (ref "LED25") (pin "C") (pinfunction "C_C") (pintype "passive"))
    )
    (net (code "74") (name "Net-(IC7-LED6)") (class "Default")
      (node (ref "IC7") (pin "16") (pinfunction "LED6_16") (pintype "output"))
      (node (ref "LED26") (pin "C") (pinfunction "C_C") (pintype "passive"))
    )
    (net (code "75") (name "Net-(IC7-LED7)") (class "Default")
      (node (ref "IC7") (pin "15") (pinfunction "LED7_15") (pintype "output"))
      (node (ref "LED27") (pin "C") (pinfunction "C_C") (pintype "passive"))
    )
    (net (code "76") (name "Net-(IC7-LED8)") (class "Default")
      (node (ref "IC7") (pin "14") (pinfunction "LED8_14") (pintype "output"))
      (node (ref "LED28") (pin "C") (pinfunction "C_C") (pintype "passive"))
    )
    (net (code "77") (name "Net-(IC7-LED9)") (class "Default")
      (node (ref "IC7") (pin "13") (pinfunction "LED9_13") (pintype "output"))
      (node (ref "LED29") (pin "C") (pinfunction "C_C") (pintype "passive"))
    )
    (net (code "78") (name "Net-(IC7-LED10)") (class "Default")
      (node (ref "IC7") (pin "12") (pinfunction "LED10_12") (pintype "output"))
      (node (ref "LED30") (pin "C") (pinfunction "C_C") (pintype "passive"))
    )
    (net (code "79") (name "Net-(IC7-REFADJ)") (class "Default")
      (node (ref "IC7") (pin "10") (pinfunction "REFADJ_10") (pintype "passive"))
      (node (ref "R5") (pin "2") (pinfunction "2_2") (pintype "passive"))
      (node (ref "R6") (pin "1") (pinfunction "1_1") (pintype "passive"))
    )
    (net (code "80") (name "Net-(IC7-REFOUT)") (class "Default")
      (node (ref "IC7") (pin "6") (pinfunction "RHI_6") (pintype "input"))
      (node (ref "IC7") (pin "8") (pinfunction "REFOUT_8") (pintype "output"))
      (node (ref "R5") (pin "1") (pinfunction "1_1") (pintype "passive"))
    )
    (net (code "81") (name "Net-(IC8-OUT)") (class "Default")
      (node (ref "D1") (pin "C") (pinfunction "C_C") (pintype "passive"))
      (node (ref "IC8") (pin "2") (pinfunction "OUT_2") (pintype "output"))
      (node (ref "L1") (pin "1") (pinfunction "1_1") (pintype "passive"))
    )
    (net (code "82") (name "Net-(JP1-Pad2)") (class "Default")
      (node (ref "JP1") (pin "2") (pinfunction "2_2") (pintype "passive"))
      (node (ref "R1") (pin "2") (pinfunction "2_2") (pintype "passive"))
    )
    (net (code "83") (name "Net-(LAUNCHCONTROL-LED-PadA)") (class "Default")
      (node (ref "LAUNCHCONTROL-LED") (pin "A") (pinfunction "A_A") (pintype "passive"))
      (node (ref "R8") (pin "2") (pinfunction "2_2") (pintype "passive"))
    )
    (net (code "84") (name "Net-(LED1-BLUE_A)") (class "Default")
      (node (ref "LED1") (pin "3") (pinfunction "BLUE_A_3") (pintype "bidirectional"))
      (node (ref "LED10") (pin "3") (pinfunction "BLUE_A_3") (pintype "bidirectional"))
      (node (ref "LED4") (pin "3") (pinfunction "BLUE_A_3") (pintype "bidirectional"))
      (node (ref "LED5") (pin "3") (pinfunction "BLUE_A_3") (pintype "bidirectional"))
      (node (ref "LED6") (pin "3") (pinfunction "BLUE_A_3") (pintype "bidirectional"))
      (node (ref "LED7") (pin "3") (pinfunction "BLUE_A_3") (pintype "bidirectional"))
      (node (ref "LED8") (pin "3") (pinfunction "BLUE_A_3") (pintype "bidirectional"))
      (node (ref "LED9") (pin "3") (pinfunction "BLUE_A_3") (pintype "bidirectional"))
      (node (ref "R2") (pin "1") (pinfunction "1_1") (pintype "passive"))
    )
    (net (code "85") (name "Net-(LED1-GREEN_A)") (class "Default")
      (node (ref "LED1") (pin "1") (pinfunction "GREEN_A_1") (pintype "bidirectional"))
      (node (ref "LED10") (pin "1") (pinfunction "GREEN_A_1") (pintype "bidirectional"))
      (node (ref "LED4") (pin "1") (pinfunction "GREEN_A_1") (pintype "bidirectional"))
      (node (ref "LED5") (pin "1") (pinfunction "GREEN_A_1") (pintype "bidirectional"))
      (node (ref "LED6") (pin "1") (pinfunction "GREEN_A_1") (pintype "bidirectional"))
      (node (ref "LED7") (pin "1") (pinfunction "GREEN_A_1") (pintype "bidirectional"))
      (node (ref "LED8") (pin "1") (pinfunction "GREEN_A_1") (pintype "bidirectional"))
      (node (ref "LED9") (pin "1") (pinfunction "GREEN_A_1") (pintype "bidirectional"))
      (node (ref "R3") (pin "1") (pinfunction "1_1") (pintype "passive"))
    )
    (net (code "86") (name "Net-(LED1-RED_A)") (class "Default")
      (node (ref "LED1") (pin "2") (pinfunction "RED_A_2") (pintype "bidirectional"))
      (node (ref "LED10") (pin "2") (pinfunction "RED_A_2") (pintype "bidirectional"))
      (node (ref "LED4") (pin "2") (pinfunction "RED_A_2") (pintype "bidirectional"))
      (node (ref "LED5") (pin "2") (pinfunction "RED_A_2") (pintype "bidirectional"))
      (node (ref "LED6") (pin "2") (pinfunction "RED_A_2") (pintype "bidirectional"))
      (node (ref "LED7") (pin "2") (pinfunction "RED_A_2") (pintype "bidirectional"))
      (node (ref "LED8") (pin "2") (pinfunction "RED_A_2") (pintype "bidirectional"))
      (node (ref "LED9") (pin "2") (pinfunction "RED_A_2") (pintype "bidirectional"))
      (node (ref "R4") (pin "1") (pinfunction "1_1") (pintype "passive"))
    )
    (net (code "87") (name "Net-(LED2-BLUE_A)") (class "Default")
      (node (ref "LED2") (pin "3") (pinfunction "BLUE_A_3") (pintype "bidirectional"))
      (node (ref "R7") (pin "2") (pinfunction "2_2") (pintype "passive"))
    )
    (net (code "88") (name "Net-(LED2-GREEN_A)") (class "Default")
      (node (ref "LED2") (pin "1") (pinfunction "GREEN_A_1") (pintype "bidirectional"))
      (node (ref "R10") (pin "2") (pinfunction "2_2") (pintype "passive"))
    )
    (net (code "89") (name "Net-(MAX7221-A)") (class "Default")
      (node (ref "MAX7221") (pin "SEG_A") (pinfunction "A_SEG_A") (pintype "bidirectional"))
      (node (ref "U$2") (pin "A") (pinfunction "A_A") (pintype "bidirectional"))
      (node (ref "U$3") (pin "A") (pinfunction "A_A") (pintype "bidirectional"))
      (node (ref "U$4") (pin "A") (pinfunction "A_A") (pintype "bidirectional"))
      (node (ref "U$5") (pin "A") (pinfunction "A_A") (pintype "bidirectional"))
      (node (ref "U$6") (pin "A") (pinfunction "A_A") (pintype "bidirectional"))
      (node (ref "U$7") (pin "A") (pinfunction "A_A") (pintype "bidirectional"))
      (node (ref "U$8") (pin "A") (pinfunction "A_A") (pintype "bidirectional"))
    )
    (net (code "90") (name "Net-(MAX7221-B)") (class "Default")
      (node (ref "MAX7221") (pin "SEG_B") (pinfunction "B_SEG_B") (pintype "bidirectional"))
      (node (ref "U$2") (pin "B") (pinfunction "B_B") (pintype "bidirectional"))
      (node (ref "U$3") (pin "B") (pinfunction "B_B") (pintype "bidirectional"))
      (node (ref "U$4") (pin "B") (pinfunction "B_B") (pintype "bidirectional"))
      (node (ref "U$5") (pin "B") (pinfunction "B_B") (pintype "bidirectional"))
      (node (ref "U$6") (pin "B") (pinfunction "B_B") (pintype "bidirectional"))
      (node (ref "U$7") (pin "B") (pinfunction "B_B") (pintype "bidirectional"))
      (node (ref "U$8") (pin "B") (pinfunction "B_B") (pintype "bidirectional"))
    )
    (net (code "91") (name "Net-(MAX7221-C)") (class "Default")
      (node (ref "MAX7221") (pin "SEG_C") (pinfunction "C_SEG_C") (pintype "bidirectional"))
      (node (ref "U$2") (pin "C") (pinfunction "C_C") (pintype "bidirectional"))
      (node (ref "U$3") (pin "C") (pinfunction "C_C") (pintype "bidirectional"))
      (node (ref "U$4") (pin "C") (pinfunction "C_C") (pintype "bidirectional"))
      (node (ref "U$5") (pin "C") (pinfunction "C_C") (pintype "bidirectional"))
      (node (ref "U$6") (pin "C") (pinfunction "C_C") (pintype "bidirectional"))
      (node (ref "U$7") (pin "C") (pinfunction "C_C") (pintype "bidirectional"))
      (node (ref "U$8") (pin "C") (pinfunction "C_C") (pintype "bidirectional"))
    )
    (net (code "92") (name "Net-(MAX7221-D)") (class "Default")
      (node (ref "MAX7221") (pin "SEG_D") (pinfunction "D_SEG_D") (pintype "bidirectional"))
      (node (ref "U$2") (pin "D") (pinfunction "D_D") (pintype "bidirectional"))
      (node (ref "U$3") (pin "D") (pinfunction "D_D") (pintype "bidirectional"))
      (node (ref "U$4") (pin "D") (pinfunction "D_D") (pintype "bidirectional"))
      (node (ref "U$5") (pin "D") (pinfunction "D_D") (pintype "bidirectional"))
      (node (ref "U$6") (pin "D") (pinfunction "D_D") (pintype "bidirectional"))
      (node (ref "U$7") (pin "D") (pinfunction "D_D") (pintype "bidirectional"))
      (node (ref "U$8") (pin "D") (pinfunction "D_D") (pintype "bidirectional"))
    )
    (net (code "93") (name "Net-(MAX7221-DP)") (class "Default")
      (node (ref "MAX7221") (pin "SEG_DP") (pinfunction "DP_SEG_DP") (pintype "bidirectional"))
      (node (ref "U$2") (pin "DP") (pinfunction "DOT_DP") (pintype "bidirectional"))
      (node (ref "U$3") (pin "DP") (pinfunction "DOT_DP") (pintype "bidirectional"))
      (node (ref "U$4") (pin "DP") (pinfunction "DOT_DP") (pintype "bidirectional"))
      (node (ref "U$5") (pin "DOT") (pinfunction "DOT_DOT") (pintype "bidirectional"))
      (node (ref "U$6") (pin "DP") (pinfunction "DOT_DP") (pintype "bidirectional"))
      (node (ref "U$7") (pin "DP") (pinfunction "DOT_DP") (pintype "bidirectional"))
      (node (ref "U$8") (pin "DP") (pinfunction "DOT_DP") (pintype "bidirectional"))
    )
    (net (code "94") (name "Net-(MAX7221-E)") (class "Default")
      (node (ref "MAX7221") (pin "SEG_E") (pinfunction "E_SEG_E") (pintype "bidirectional"))
      (node (ref "U$2") (pin "E") (pinfunction "E_E") (pintype "bidirectional"))
      (node (ref "U$3") (pin "E") (pinfunction "E_E") (pintype "bidirectional"))
      (node (ref "U$4") (pin "E") (pinfunction "E_E") (pintype "bidirectional"))
      (node (ref "U$5") (pin "E") (pinfunction "E_E") (pintype "bidirectional"))
      (node (ref "U$6") (pin "E") (pinfunction "E_E") (pintype "bidirectional"))
      (node (ref "U$7") (pin "E") (pinfunction "E_E") (pintype "bidirectional"))
      (node (ref "U$8") (pin "E") (pinfunction "E_E") (pintype "bidirectional"))
    )
    (net (code "95") (name "Net-(MAX7221-F)") (class "Default")
      (node (ref "MAX7221") (pin "SEG_F") (pinfunction "F_SEG_F") (pintype "bidirectional"))
      (node (ref "U$2") (pin "F") (pinfunction "F_F") (pintype "bidirectional"))
      (node (ref "U$3") (pin "F") (pinfunction "F_F") (pintype "bidirectional"))
      (node (ref "U$4") (pin "F") (pinfunction "F_F") (pintype "bidirectional"))
      (node (ref "U$5") (pin "F") (pinfunction "F_F") (pintype "bidirectional"))
      (node (ref "U$6") (pin "F") (pinfunction "F_F") (pintype "bidirectional"))
      (node (ref "U$7") (pin "F") (pinfunction "F_F") (pintype "bidirectional"))
      (node (ref "U$8") (pin "F") (pinfunction "F_F") (pintype "bidirectional"))
    )
    (net (code "96") (name "Net-(MAX7221-G)") (class "Default")
      (node (ref "MAX7221") (pin "SEG_G") (pinfunction "G_SEG_G") (pintype "bidirectional"))
      (node (ref "U$2") (pin "G") (pinfunction "G_G") (pintype "bidirectional"))
      (node (ref "U$3") (pin "G") (pinfunction "G_G") (pintype "bidirectional"))
      (node (ref "U$4") (pin "G") (pinfunction "G_G") (pintype "bidirectional"))
      (node (ref "U$5") (pin "G") (pinfunction "G_G") (pintype "bidirectional"))
      (node (ref "U$6") (pin "G") (pinfunction "G_G") (pintype "bidirectional"))
      (node (ref "U$7") (pin "G") (pinfunction "G_G") (pintype "bidirectional"))
      (node (ref "U$8") (pin "G") (pinfunction "G_G") (pintype "bidirectional"))
    )
    (net (code "97") (name "Net-(MAX7221-PadISET)") (class "Default")
      (node (ref "MAX7221") (pin "ISET") (pinfunction "ISET_ISET") (pintype "bidirectional"))
      (node (ref "R11") (pin "2") (pinfunction "2_2") (pintype "passive"))
    )
    (net (code "98") (name "Net-(U$2-GN)") (class "Default")
      (node (ref "MAX7221") (pin "DIG0") (pinfunction "DIG0_DIG0") (pintype "bidirectional"))
      (node (ref "U$2") (pin "GND") (pinfunction "GN_GND") (pintype "bidirectional"))
      (node (ref "U$2") (pin "GND2") (pinfunction "GND_GND2") (pintype "bidirectional"))
    )
    (net (code "99") (name "Net-(U$3-GN)") (class "Default")
      (node (ref "MAX7221") (pin "DIG1") (pinfunction "DIG1_DIG1") (pintype "bidirectional"))
      (node (ref "U$3") (pin "GND") (pinfunction "GN_GND") (pintype "bidirectional"))
      (node (ref "U$3") (pin "GND2") (pinfunction "GND_GND2") (pintype "bidirectional"))
    )
    (net (code "100") (name "Net-(U$4-GN)") (class "Default")
      (node (ref "MAX7221") (pin "DIG2") (pinfunction "DIG2_DIG2") (pintype "bidirectional"))
      (node (ref "U$4") (pin "GND") (pinfunction "GN_GND") (pintype "bidirectional"))
      (node (ref "U$4") (pin "GND2") (pinfunction "GND_GND2") (pintype "bidirectional"))
    )
    (net (code "101") (name "Net-(U$5-GN)") (class "Default")
      (node (ref "MAX7221") (pin "DIG3") (pinfunction "DIG3_DIG3") (pintype "bidirectional"))
      (node (ref "U$5") (pin "GND") (pinfunction "GN_GND") (pintype "bidirectional"))
      (node (ref "U$5") (pin "GND2") (pinfunction "GND_GND2") (pintype "bidirectional"))
    )
    (net (code "102") (name "Net-(U$6-GN)") (class "Default")
      (node (ref "MAX7221") (pin "DIG4") (pinfunction "DIG4_DIG4") (pintype "bidirectional"))
      (node (ref "U$6") (pin "GND") (pinfunction "GN_GND") (pintype "bidirectional"))
      (node (ref "U$6") (pin "GND2") (pinfunction "GND_GND2") (pintype "bidirectional"))
    )
    (net (code "103") (name "Net-(U$7-GN)") (class "Default")
      (node (ref "MAX7221") (pin "DIG5") (pinfunction "DIG5_DIG5") (pintype "bidirectional"))
      (node (ref "U$7") (pin "GND") (pinfunction "GN_GND") (pintype "bidirectional"))
      (node (ref "U$7") (pin "GND2") (pinfunction "GND_GND2") (pintype "bidirectional"))
    )
    (net (code "104") (name "Net-(U$8-GN)") (class "Default")
      (node (ref "MAX7221") (pin "DIG6") (pinfunction "DIG6_DIG6") (pintype "bidirectional"))
      (node (ref "U$8") (pin "GND") (pinfunction "GN_GND") (pintype "bidirectional"))
      (node (ref "U$8") (pin "GND2") (pinfunction "GND_GND2") (pintype "bidirectional"))
    )
    (net (code "105") (name "PE") (class "Default")
      (node (ref "C1") (pin "1") (pinfunction "1_1") (pintype "passive"))
      (node (ref "C10") (pin "2") (pinfunction "2_2") (pintype "passive"))
      (node (ref "C19") (pin "2") (pinfunction "2_2") (pintype "passive"))
      (node (ref "C2") (pin "1") (pinfunction "1_1") (pintype "passive"))
      (node (ref "C3") (pin "-") (pinfunction "-_-") (pintype "passive"))
      (node (ref "C4") (pin "-") (pinfunction "-_-") (pintype "passive"))
      (node (ref "C5") (pin "2") (pinfunction "2_2") (pintype "passive"))
      (node (ref "C6") (pin "2") (pinfunction "2_2") (pintype "passive"))
      (node (ref "C7") (pin "2") (pinfunction "2_2") (pintype "passive"))
      (node (ref "C8") (pin "2") (pinfunction "2_2") (pintype "passive"))
      (node (ref "C9") (pin "2") (pinfunction "2_2") (pintype "passive"))
      (node (ref "D1") (pin "A") (pinfunction "A_A") (pintype "passive"))
      (node (ref "IC2") (pin "22") (pinfunction "GND_22") (pintype "power_in"))
      (node (ref "IC2") (pin "53") (pinfunction "GND_53") (pintype "power_in"))
      (node (ref "IC2") (pin "63") (pinfunction "GND_63") (pintype "power_in"))
      (node (ref "IC3") (pin "2") (pinfunction "GND_2") (pintype "power_in"))
      (node (ref "IC3") (pin "8") (pinfunction "RS_8") (pintype "input"))
      (node (ref "IC5") (pin "4") (pinfunction "G2A_4") (pintype "input"))
      (node (ref "IC5") (pin "5") (pinfunction "G2B_5") (pintype "input"))
      (node (ref "IC5") (pin "8") (pinfunction "GND_8") (pintype "power_in"))
      (node (ref "IC6") (pin "10") (pinfunction "REFADJ_10") (pintype "passive"))
      (node (ref "IC6") (pin "2") (pinfunction "V-_2") (pintype "power_in"))
      (node (ref "IC6") (pin "4") (pinfunction "RLO_4") (pintype "input"))
      (node (ref "IC7") (pin "2") (pinfunction "V-_2") (pintype "power_in"))
      (node (ref "IC8") (pin "3") (pinfunction "GND_3") (pintype "power_in"))
      (node (ref "IC8") (pin "5") (pinfunction "EN_5") (pintype "input"))
      (node (ref "IC8") (pin "6") (pinfunction "GND_6") (pintype "power_in"))
      (node (ref "JP6") (pin "3") (pinfunction "3_3") (pintype "passive"))
      (node (ref "JP6") (pin "4") (pinfunction "4_4") (pintype "passive"))
      (node (ref "LAUNCHCONTROL-LED") (pin "C") (pinfunction "C_C") (pintype "passive"))
      (node (ref "LED2") (pin "4") (pinfunction "BLUE_C_4") (pintype "bidirectional"))
      (node (ref "LED2") (pin "5") (pinfunction "RED_C_5") (pintype "bidirectional"))
      (node (ref "LED2") (pin "6") (pinfunction "GREEN_C_6") (pintype "bidirectional"))
      (node (ref "MAX7221") (pin "GND") (pinfunction "GND_GND") (pintype "bidirectional"))
      (node (ref "MAX7221") (pin "GND1") (pinfunction "GND1_GND1") (pintype "bidirectional"))
      (node (ref "R12") (pin "1") (pinfunction "1_1") (pintype "passive"))
      (node (ref "R13") (pin "1") (pinfunction "1_1") (pintype "passive"))
      (node (ref "R14") (pin "2") (pinfunction "2_2") (pintype "passive"))
      (node (ref "R15") (pin "2") (pinfunction "2_2") (pintype "passive"))
      (node (ref "R16") (pin "2") (pinfunction "2_2") (pintype "passive"))
      (node (ref "R17") (pin "2") (pinfunction "2_2") (pintype "passive"))
      (node (ref "R18") (pin "2") (pinfunction "2_2") (pintype "passive"))
      (node (ref "R19") (pin "1") (pinfunction "1_1") (pintype "passive"))
      (node (ref "R20") (pin "1") (pinfunction "1_1") (pintype "passive"))
      (node (ref "R21") (pin "2") (pinfunction "2_2") (pintype "passive"))
      (node (ref "R22") (pin "2") (pinfunction "2_2") (pintype "passive"))
      (node (ref "R23") (pin "2") (pinfunction "2_2") (pintype "passive"))
      (node (ref "R24") (pin "2") (pinfunction "2_2") (pintype "passive"))
      (node (ref "R25") (pin "2") (pinfunction "2_2") (pintype "passive"))
      (node (ref "R26") (pin "2") (pinfunction "2_2") (pintype "passive"))
      (node (ref "R27") (pin "2") (pinfunction "2_2") (pintype "passive"))
      (node (ref "R28") (pin "2") (pinfunction "2_2") (pintype "passive"))
      (node (ref "R6") (pin "2") (pinfunction "2_2") (pintype "passive"))
      (node (ref "R9") (pin "2") (pinfunction "2_2") (pintype "passive"))
      (node (ref "U$9") (pin "GND") (pinfunction "GND_GND") (pintype "bidirectional"))
      (node (ref "UART1") (pin "3") (pinfunction "3_3") (pintype "passive"))
    )
    (net (code "106") (name "VCC") (class "Default")
      (node (ref "C3") (pin "+") (pinfunction "+_+") (pintype "passive"))
      (node (ref "IC8") (pin "1") (pinfunction "IN_1") (pintype "input"))
      (node (ref "JP6") (pin "5") (pinfunction "5_5") (pintype "passive"))
      (node (ref "JP6") (pin "6") (pinfunction "6_6") (pintype "passive"))
    )
    (net (code "107") (name "unconnected-(IC2-(A8)PC0-Pad35)") (class "Default")
      (node (ref "IC2") (pin "35") (pinfunction "(A8)PC0_35") (pintype "output"))
    )
    (net (code "108") (name "unconnected-(IC2-(A9)PC1-Pad36)") (class "Default")
      (node (ref "IC2") (pin "36") (pinfunction "(A9)PC1_36") (pintype "output"))
    )
    (net (code "109") (name "unconnected-(IC2-(A10)PC2-Pad37)") (class "Default")
      (node (ref "IC2") (pin "37") (pinfunction "(A10)PC2_37") (pintype "output"))
    )
    (net (code "110") (name "unconnected-(IC2-(A11)PC3-Pad38)") (class "Default")
      (node (ref "IC2") (pin "38") (pinfunction "(A11)PC3_38") (pintype "output"))
    )
    (net (code "111") (name "unconnected-(IC2-(A12)PC4-Pad39)") (class "Default")
      (node (ref "IC2") (pin "39") (pinfunction "(A12)PC4_39") (pintype "output"))
    )
    (net (code "112") (name "unconnected-(IC2-(IC1)PD4-Pad29)") (class "Default")
      (node (ref "IC2") (pin "29") (pinfunction "(IC1)PD4_29") (pintype "bidirectional"))
    )
    (net (code "113") (name "unconnected-(IC2-(MISO)PB3-Pad13)") (class "Default")
      (node (ref "IC2") (pin "13") (pinfunction "(MISO)PB3_13") (pintype "bidirectional"))
    )
    (net (code "114") (name "unconnected-(IC2-(T2)PD7-Pad32)") (class "Default")
      (node (ref "IC2") (pin "32") (pinfunction "(T2)PD7_32") (pintype "bidirectional"))
    )
    (net (code "115") (name "unconnected-(IC2-PEN-Pad1)") (class "Default")
      (node (ref "IC2") (pin "1") (pinfunction "PEN_1") (pintype "input"))
    )
    (net (code "116") (name "unconnected-(IC2-PF0(ADC0)-Pad61)") (class "Default")
      (node (ref "IC2") (pin "61") (pinfunction "PF0(ADC0)_61") (pintype "input"))
    )
    (net (code "117") (name "unconnected-(IC2-PF1(ADC1)-Pad60)") (class "Default")
      (node (ref "IC2") (pin "60") (pinfunction "PF1(ADC1)_60") (pintype "input"))
    )
    (net (code "118") (name "unconnected-(IC2-PG0(WR)-Pad33)") (class "Default")
      (node (ref "IC2") (pin "33") (pinfunction "PG0(WR)_33") (pintype "bidirectional"))
    )
    (net (code "119") (name "unconnected-(IC2-PG1(RD)-Pad34)") (class "Default")
      (node (ref "IC2") (pin "34") (pinfunction "PG1(RD)_34") (pintype "bidirectional"))
    )
    (net (code "120") (name "unconnected-(IC2-PG2(ALE)-Pad43)") (class "Default")
      (node (ref "IC2") (pin "43") (pinfunction "PG2(ALE)_43") (pintype "bidirectional"))
    )
    (net (code "121") (name "unconnected-(IC2-PG3(TOSC2)-Pad18)") (class "Default")
      (node (ref "IC2") (pin "18") (pinfunction "PG3(TOSC2)_18") (pintype "bidirectional"))
    )
    (net (code "122") (name "unconnected-(IC2-PG4(TOSC1)-Pad19)") (class "Default")
      (node (ref "IC2") (pin "19") (pinfunction "PG4(TOSC1)_19") (pintype "bidirectional"))
    )
    (net (code "123") (name "unconnected-(IC3-VREF-Pad5)") (class "Default")
      (node (ref "IC3") (pin "5") (pinfunction "VREF_5") (pintype "output"))
    )
    (net (code "124") (name "unconnected-(LED2-RED_A-Pad2)") (class "Default")
      (node (ref "LED2") (pin "2") (pinfunction "RED_A_2") (pintype "bidirectional"))
    )
    (net (code "125") (name "unconnected-(MAX7221-PadDIG7)") (class "Default")
      (node (ref "MAX7221") (pin "DIG7") (pinfunction "DIG7_DIG7") (pintype "bidirectional"))
    )
    (net (code "126") (name "unconnected-(MAX7221-PadDOUT)") (class "Default")
      (node (ref "MAX7221") (pin "DOUT") (pinfunction "DOUT_DOUT") (pintype "bidirectional"))
    )
  )
)
